# SMA-Q2_replacement_board_v2_3different.net
KiCad netlist of a schematic drawn in EAGLE
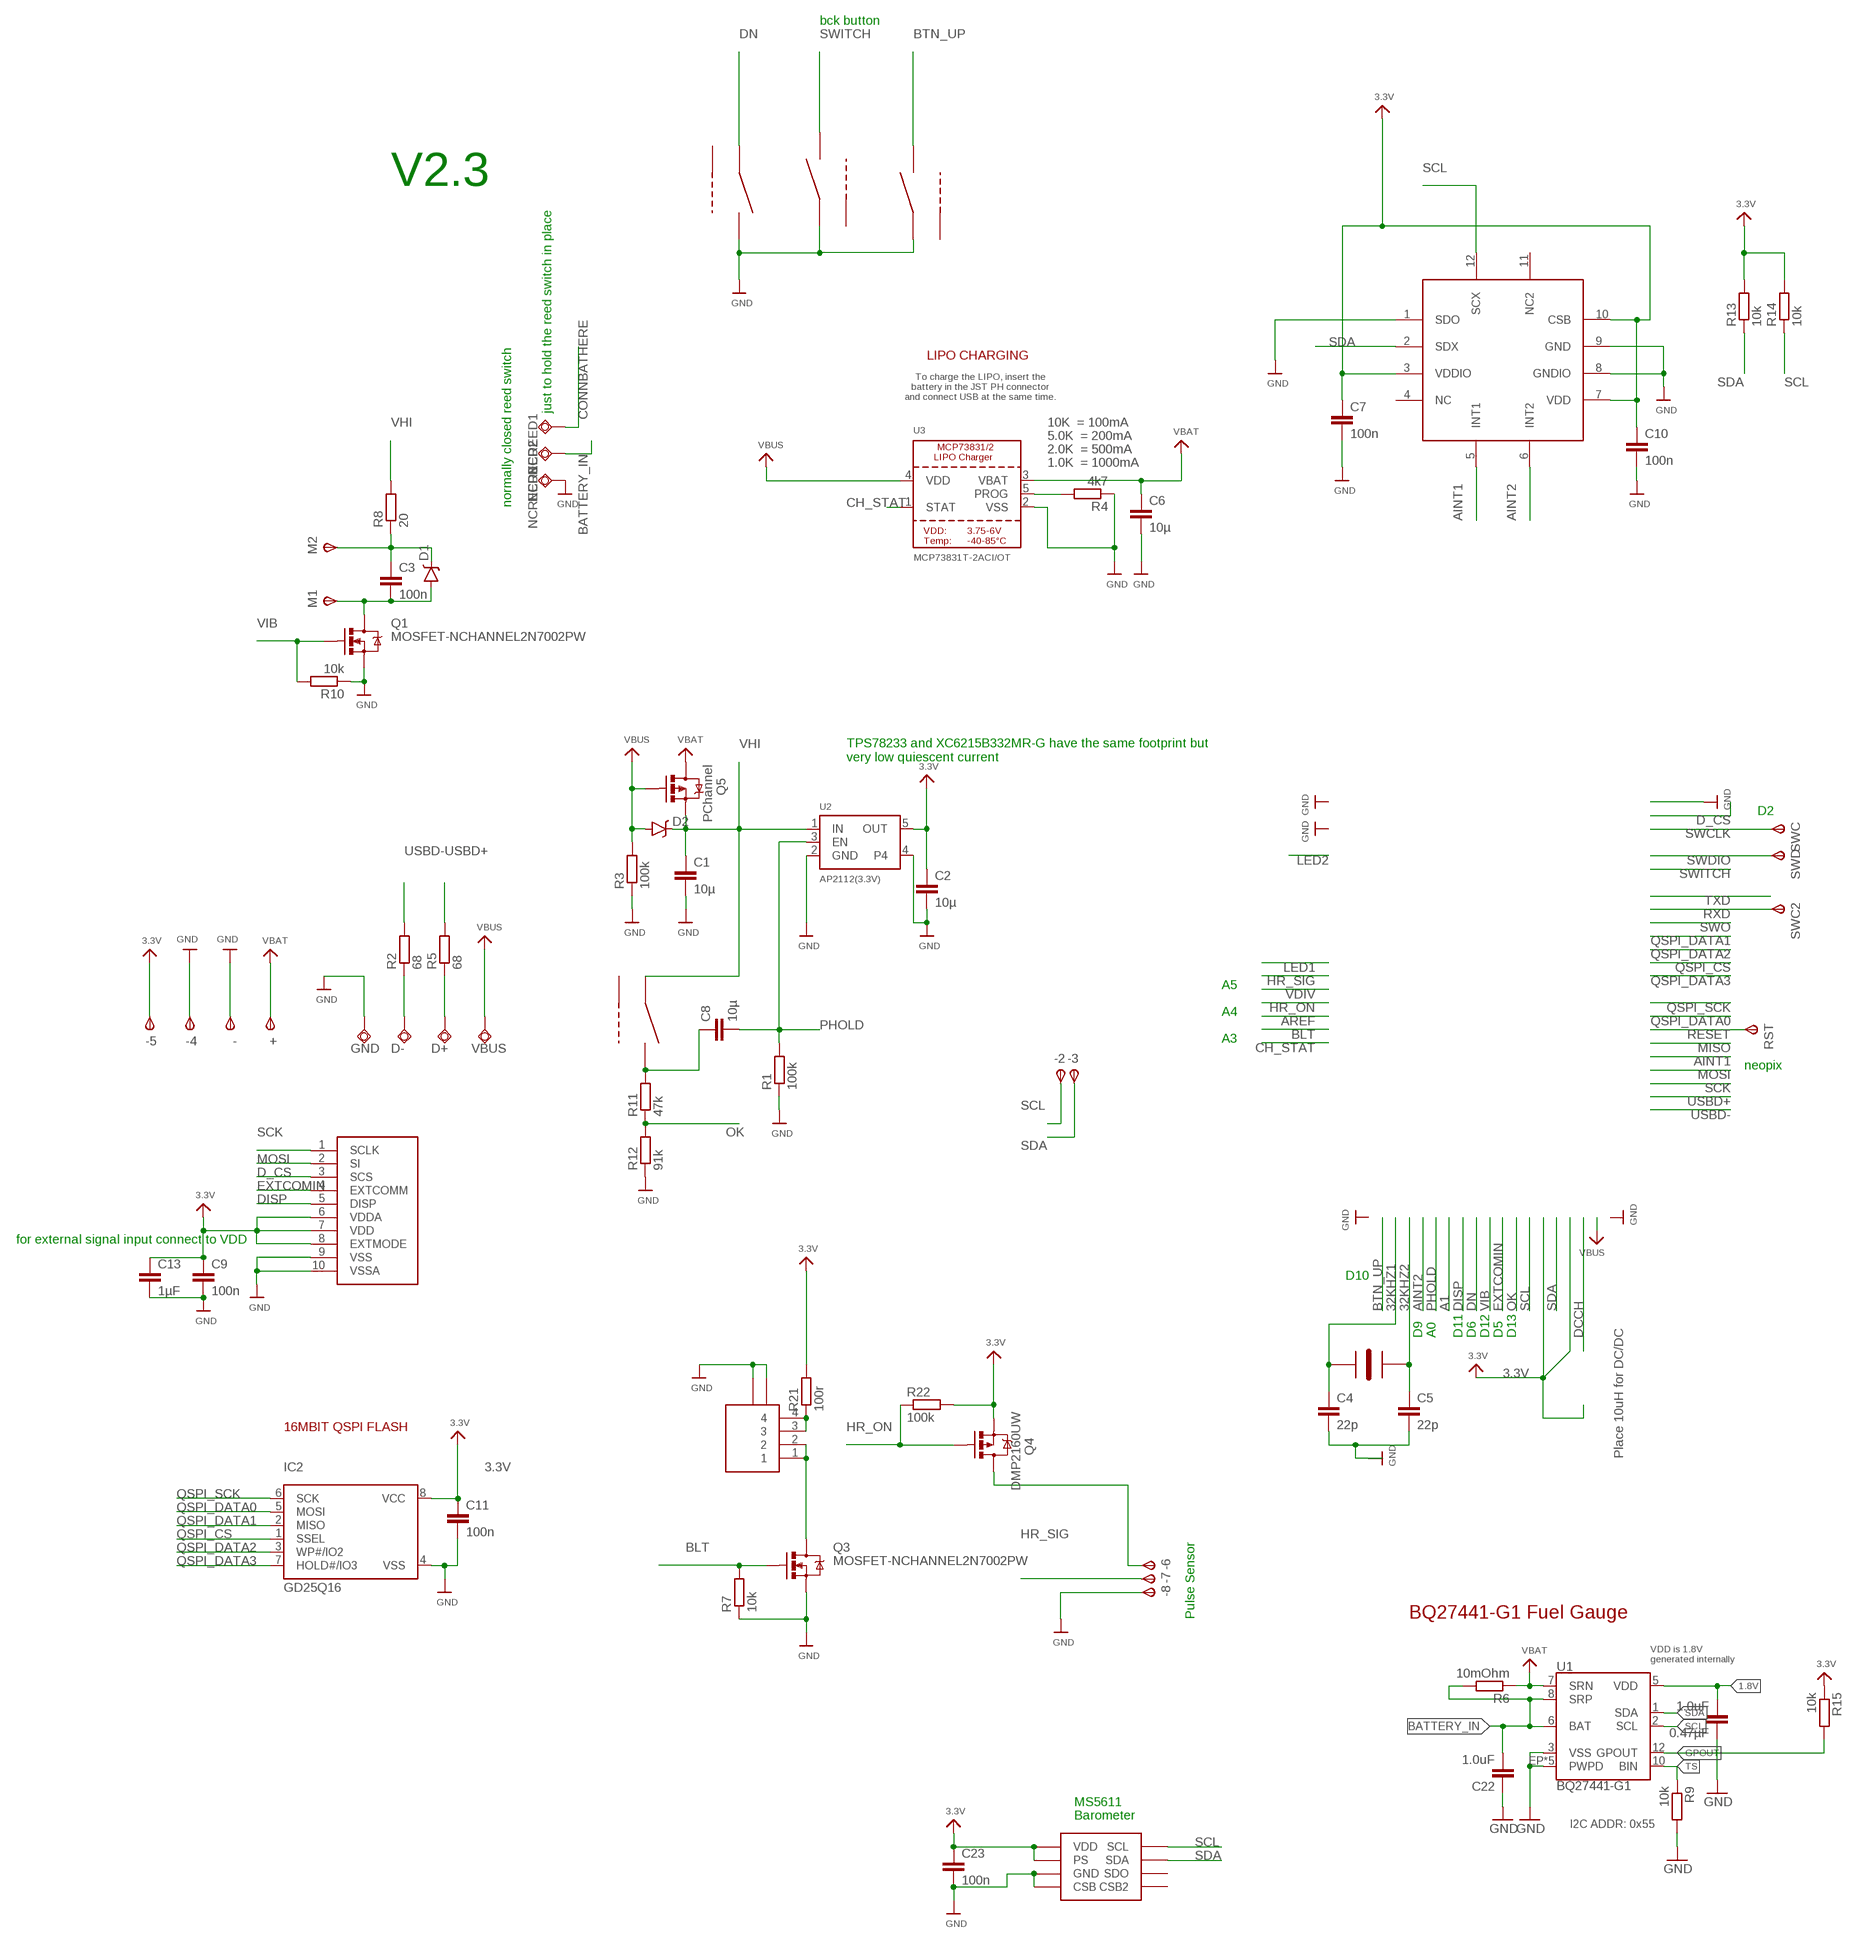
[diagram p0: schematic, sheet 1, part 1 of 2]
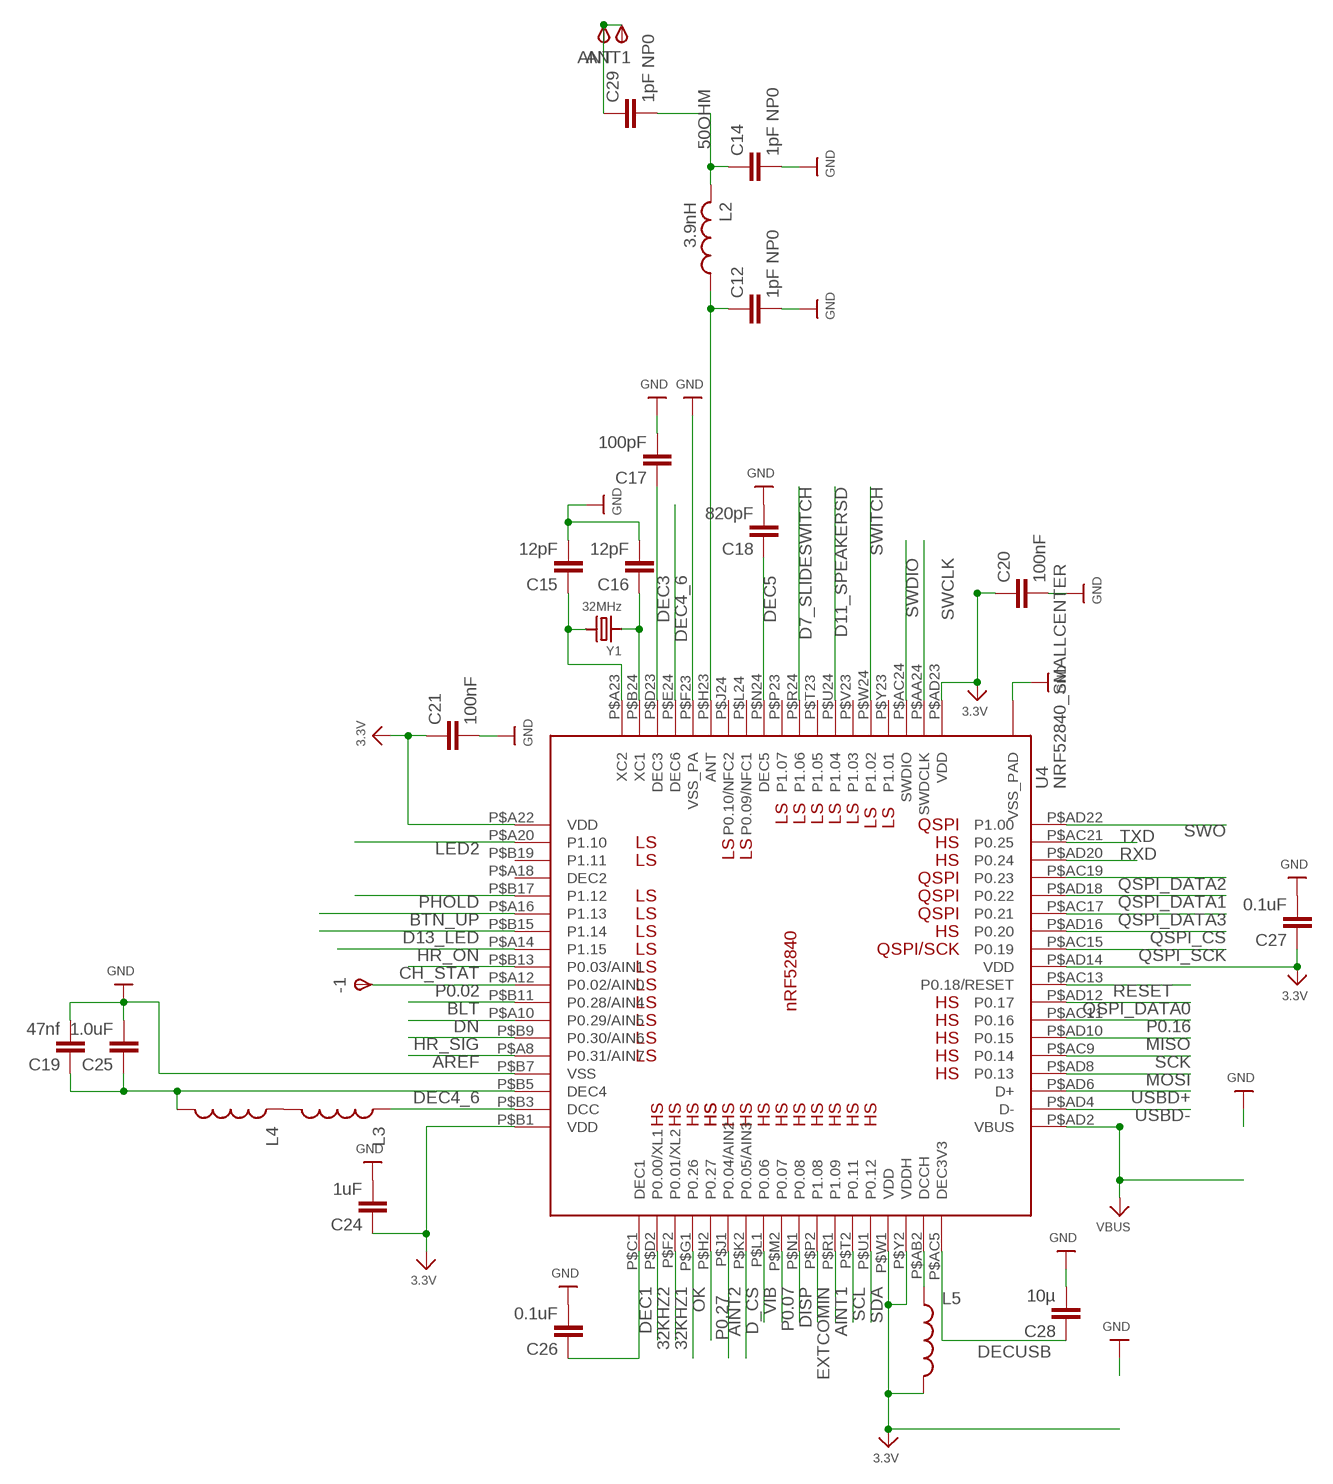
[diagram p1: schematic, sheet 1, part 2 of 2]

(export (version "E")
  (design (tool "Eeschema 10.0.6"))
  (components
    (comp (ref "+")
      (value "TPSTP09R")
      (footprint "eagle-import:TP09R")
      (libsource (lib "eagle-import") (part "TPSTP09R"))
    )
    (comp (ref "-")
      (value "TPSTP09R")
      (footprint "eagle-import:TP09R")
      (libsource (lib "eagle-import") (part "TPSTP09R"))
    )
    (comp (ref "-1")
      (value "TPSTP09R")
      (footprint "eagle-import:TP09R")
      (libsource (lib "eagle-import") (part "TPSTP09R"))
    )
    (comp (ref "-2")
      (value "TPSTP09R")
      (footprint "eagle-import:TP09R")
      (libsource (lib "eagle-import") (part "TPSTP09R"))
    )
    (comp (ref "-3")
      (value "TPSTP09R")
      (footprint "eagle-import:TP09R")
      (libsource (lib "eagle-import") (part "TPSTP09R"))
    )
    (comp (ref "-4")
      (value "TPSTP09R")
      (footprint "eagle-import:TP09R")
      (libsource (lib "eagle-import") (part "TPSTP09R"))
    )
    (comp (ref "-5")
      (value "TPSTP09R")
      (footprint "eagle-import:TP09R")
      (libsource (lib "eagle-import") (part "TPSTP09R"))
    )
    (comp (ref "-6")
      (value "TPSTP09R")
      (footprint "eagle-import:TP09R")
      (libsource (lib "eagle-import") (part "TPSTP09R"))
    )
    (comp (ref "-7")
      (value "TPSTP09R")
      (footprint "eagle-import:TP09R")
      (libsource (lib "eagle-import") (part "TPSTP09R"))
    )
    (comp (ref "-8")
      (value "TPSTP09R")
      (footprint "eagle-import:TP09R")
      (libsource (lib "eagle-import") (part "TPSTP09R"))
    )
    (comp (ref "0.47µF")
      (value "1.0uF")
      (footprint "eagle-import:RESC0603_N")
      (libsource (lib "eagle-import") (part "CAPACITOR_0603_N"))
    )
    (comp (ref "ANT")
      (value "TPSTP19SQ")
      (footprint "eagle-import:TP19SQ")
      (libsource (lib "eagle-import") (part "TPSTP19SQ"))
    )
    (comp (ref "ANT1")
      (value "TPSTP19SQ")
      (footprint "eagle-import:TP19SQ")
      (libsource (lib "eagle-import") (part "TPSTP19SQ"))
    )
    (comp (ref "C1")
      (value "10µ")
      (footprint "eagle-import:C0603")
      (libsource (lib "eagle-import") (part "C-EUC0603"))
    )
    (comp (ref "C2")
      (value "10µ")
      (footprint "eagle-import:C0603")
      (libsource (lib "eagle-import") (part "C-EUC0603"))
    )
    (comp (ref "C3")
      (value "100n")
      (footprint "eagle-import:C0402")
      (libsource (lib "eagle-import") (part "C-EUC0402"))
    )
    (comp (ref "C4")
      (value "22p")
      (footprint "eagle-import:C0402")
      (libsource (lib "eagle-import") (part "C-EUC0402"))
    )
    (comp (ref "C5")
      (value "22p")
      (footprint "eagle-import:C0402")
      (libsource (lib "eagle-import") (part "C-EUC0402"))
    )
    (comp (ref "C6")
      (value "10µ")
      (footprint "eagle-import:C0603")
      (libsource (lib "eagle-import") (part "C-EUC0603"))
    )
    (comp (ref "C7")
      (value "100n")
      (footprint "eagle-import:C0402")
      (libsource (lib "eagle-import") (part "C-EUC0402"))
    )
    (comp (ref "C8")
      (value "10µ")
      (footprint "eagle-import:C0603")
      (libsource (lib "eagle-import") (part "C-EUC0603"))
    )
    (comp (ref "C9")
      (value "100n")
      (footprint "eagle-import:C0402")
      (libsource (lib "eagle-import") (part "C-EUC0402"))
    )
    (comp (ref "C10")
      (value "100n")
      (footprint "eagle-import:C0402")
      (libsource (lib "eagle-import") (part "C-EUC0402"))
    )
    (comp (ref "C11")
      (value "100n")
      (footprint "eagle-import:C0402")
      (libsource (lib "eagle-import") (part "C-EUC0402"))
    )
    (comp (ref "C12")
      (value "1pF NP0")
      (footprint "eagle-import:RESC0402_N")
      (libsource (lib "eagle-import") (part "CAPACITOR_0402_N"))
    )
    (comp (ref "C13")
      (value "1µF")
      (footprint "eagle-import:C0402")
      (libsource (lib "eagle-import") (part "C-EUC0402"))
    )
    (comp (ref "C14")
      (value "1pF NP0")
      (footprint "eagle-import:RESC0402_N")
      (libsource (lib "eagle-import") (part "CAPACITOR_0402_N"))
    )
    (comp (ref "C15")
      (value "12pF")
      (footprint "eagle-import:RESC0402_N")
      (libsource (lib "eagle-import") (part "CAPACITOR_0402_N"))
    )
    (comp (ref "C16")
      (value "12pF")
      (footprint "eagle-import:RESC0402_N")
      (libsource (lib "eagle-import") (part "CAPACITOR_0402_N"))
    )
    (comp (ref "C17")
      (value "100pF")
      (footprint "eagle-import:RESC0402_N")
      (libsource (lib "eagle-import") (part "CAPACITOR_0402_N"))
    )
    (comp (ref "C18")
      (value "820pF")
      (footprint "eagle-import:RESC0402_N")
      (libsource (lib "eagle-import") (part "CAPACITOR_0402_N"))
    )
    (comp (ref "C19")
      (value "47nf")
      (footprint "eagle-import:RESC0603_N")
      (libsource (lib "eagle-import") (part "CAPACITOR_0603_N"))
    )
    (comp (ref "C20")
      (value "100nF")
      (footprint "eagle-import:RESC0402_N")
      (libsource (lib "eagle-import") (part "CAPACITOR_0402_N"))
    )
    (comp (ref "C21")
      (value "100nF")
      (footprint "eagle-import:RESC0402_N")
      (libsource (lib "eagle-import") (part "CAPACITOR_0402_N"))
    )
    (comp (ref "C22")
      (value "1.0uF")
      (footprint "eagle-import:RESC0603_N")
      (libsource (lib "eagle-import") (part "CAPACITOR_0603_N"))
    )
    (comp (ref "C23")
      (value "100n")
      (footprint "eagle-import:C0402")
      (libsource (lib "eagle-import") (part "C-EUC0402"))
    )
    (comp (ref "C24")
      (value "1uF")
      (footprint "eagle-import:RESC0603_N")
      (libsource (lib "eagle-import") (part "CAPACITOR_0603_N"))
    )
    (comp (ref "C25")
      (value "1.0uF")
      (footprint "eagle-import:RESC0603_N")
      (libsource (lib "eagle-import") (part "CAPACITOR_0603_N"))
    )
    (comp (ref "C26")
      (value "0.1uF")
      (footprint "eagle-import:RESC0603_N")
      (libsource (lib "eagle-import") (part "CAPACITOR_0603_N"))
    )
    (comp (ref "C27")
      (value "0.1uF")
      (footprint "eagle-import:RESC0402_N")
      (libsource (lib "eagle-import") (part "CAPACITOR_0402_N"))
    )
    (comp (ref "C28")
      (value "10µ")
      (footprint "eagle-import:C0603")
      (libsource (lib "eagle-import") (part "C-EUC0603"))
    )
    (comp (ref "C29")
      (value "1pF NP0")
      (footprint "eagle-import:RESC0402_N")
      (libsource (lib "eagle-import") (part "CAPACITOR_0402_N"))
    )
    (comp (ref "D+")
      (value "TPSQTP20R")
      (footprint "eagle-import:TP20R")
      (libsource (lib "eagle-import") (part "TPSQTP20R"))
    )
    (comp (ref "D-")
      (value "TPSQTP20R")
      (footprint "eagle-import:TP20R")
      (libsource (lib "eagle-import") (part "TPSQTP20R"))
    )
    (comp (ref "D1")
      (value "BAT20J")
      (footprint "eagle-import:SOD-323")
      (libsource (lib "eagle-import") (part "DIODE-SCHOTTKY-BAT20J"))
    )
    (comp (ref "D2")
      (value "BAT20J")
      (footprint "eagle-import:SOD-323")
      (libsource (lib "eagle-import") (part "DIODE-SCHOTTKY-BAT20J"))
    )
    (comp (ref "DWN")
      (value "LS12T2")
      (footprint "eagle-import:LS12T2")
      (libsource (lib "eagle-import") (part "LS12T2"))
    )
    (comp (ref "DWN1")
      (value "LS12T2")
      (footprint "eagle-import:LS12T2")
      (libsource (lib "eagle-import") (part "LS12T2"))
    )
    (comp (ref "DWN2")
      (value "LS12T2")
      (footprint "eagle-import:LS12T2")
      (libsource (lib "eagle-import") (part "LS12T2"))
    )
    (comp (ref "DWN3")
      (value "LS12T2")
      (footprint "eagle-import:LS12T2")
      (libsource (lib "eagle-import") (part "LS12T2"))
    )
    (comp (ref "GND")
      (value "TPSQTP20R")
      (footprint "eagle-import:TP20R")
      (libsource (lib "eagle-import") (part "TPSQTP20R"))
    )
    (comp (ref "IC2")
      (value "GD25Q16")
      (footprint "eagle-import:USON8")
      (libsource (lib "eagle-import") (part "SPIFLASH_8PINUX"))
    )
    (comp (ref "L2")
      (value "3.9nH")
      (footprint "eagle-import:RESC0402_N")
      (libsource (lib "eagle-import") (part "INDUCTOR_0402_N"))
    )
    (comp (ref "L3")
      (value "INDUCTOR30OHM,1.8A")
      (footprint "eagle-import:0603")
      (libsource (lib "eagle-import") (part "INDUCTOR30OHM,1.8A"))
    )
    (comp (ref "L4")
      (value "INDUCTOR0402")
      (footprint "eagle-import:C0402")
      (libsource (lib "eagle-import") (part "INDUCTOR0402"))
    )
    (comp (ref "L5")
      (value "INDUCTOR30OHM,1.8A")
      (footprint "eagle-import:0603")
      (libsource (lib "eagle-import") (part "INDUCTOR30OHM,1.8A"))
    )
    (comp (ref "M1")
      (value "TPSTP09R")
      (footprint "eagle-import:TP09R")
      (libsource (lib "eagle-import") (part "TPSTP09R"))
    )
    (comp (ref "M2")
      (value "TPSTP09R")
      (footprint "eagle-import:TP09R")
      (libsource (lib "eagle-import") (part "TPSTP09R"))
    )
    (comp (ref "NCREED1")
      (value "TPSQTP20R")
      (footprint "eagle-import:TP20R")
      (libsource (lib "eagle-import") (part "TPSQTP20R"))
    )
    (comp (ref "NCREED2")
      (value "TPSQTP20R")
      (footprint "eagle-import:TP20R")
      (libsource (lib "eagle-import") (part "TPSQTP20R"))
    )
    (comp (ref "NCREED3")
      (value "TPSQTP20R")
      (footprint "eagle-import:TP20R")
      (libsource (lib "eagle-import") (part "TPSQTP20R"))
    )
    (comp (ref "Q1")
      (value "MOSFET-NCHANNEL2N7002PW")
      (footprint "eagle-import:SOT323")
      (libsource (lib "eagle-import") (part "MOSFET-NCHANNEL2N7002PW"))
    )
    (comp (ref "Q3")
      (value "MOSFET-NCHANNEL2N7002PW")
      (footprint "eagle-import:SOT323")
      (libsource (lib "eagle-import") (part "MOSFET-NCHANNEL2N7002PW"))
    )
    (comp (ref "Q4")
      (value "DMP2160UW")
      (footprint "eagle-import:SOT323")
      (libsource (lib "eagle-import") (part "MOSFET-P-CHANNEL-DMP2160UW"))
    )
    (comp (ref "Q5")
      (value "PChannel")
      (footprint "eagle-import:SOT323")
      (libsource (lib "eagle-import") (part "MOSFET-P-CHANNEL-DMP2160UW"))
    )
    (comp (ref "R1")
      (value "100k")
      (footprint "eagle-import:R0402")
      (libsource (lib "eagle-import") (part "R-EU_R0402"))
    )
    (comp (ref "R2")
      (value "68")
      (footprint "eagle-import:R0402")
      (libsource (lib "eagle-import") (part "R-EU_R0402"))
    )
    (comp (ref "R3")
      (value "100k")
      (footprint "eagle-import:R0402")
      (libsource (lib "eagle-import") (part "R-EU_R0402"))
    )
    (comp (ref "R4")
      (value "4k7")
      (footprint "eagle-import:R0402")
      (libsource (lib "eagle-import") (part "R-EU_R0402"))
    )
    (comp (ref "R5")
      (value "68")
      (footprint "eagle-import:R0402")
      (libsource (lib "eagle-import") (part "R-EU_R0402"))
    )
    (comp (ref "R6")
      (value "10mOhm")
      (footprint "eagle-import:R0402")
      (libsource (lib "eagle-import") (part "R-EU_R0402"))
    )
    (comp (ref "R7")
      (value "10k")
      (footprint "eagle-import:R0402")
      (libsource (lib "eagle-import") (part "R-EU_R0402"))
    )
    (comp (ref "R8")
      (value "20")
      (footprint "eagle-import:R0402")
      (libsource (lib "eagle-import") (part "R-EU_R0402"))
    )
    (comp (ref "R9")
      (value "10k")
      (footprint "eagle-import:R0402")
      (libsource (lib "eagle-import") (part "R-EU_R0402"))
    )
    (comp (ref "R10")
      (value "10k")
      (footprint "eagle-import:R0402")
      (libsource (lib "eagle-import") (part "R-EU_R0402"))
    )
    (comp (ref "R11")
      (value "47k")
      (footprint "eagle-import:R0402")
      (libsource (lib "eagle-import") (part "R-EU_R0402"))
    )
    (comp (ref "R12")
      (value "91k")
      (footprint "eagle-import:R0402")
      (libsource (lib "eagle-import") (part "R-EU_R0402"))
    )
    (comp (ref "R13")
      (value "10k")
      (footprint "eagle-import:R0402")
      (libsource (lib "eagle-import") (part "R-EU_R0402"))
    )
    (comp (ref "R14")
      (value "10k")
      (footprint "eagle-import:R0402")
      (libsource (lib "eagle-import") (part "R-EU_R0402"))
    )
    (comp (ref "R15")
      (value "10k")
      (footprint "eagle-import:R0402")
      (libsource (lib "eagle-import") (part "R-EU_R0402"))
    )
    (comp (ref "R21")
      (value "100r")
      (footprint "eagle-import:R0402")
      (libsource (lib "eagle-import") (part "R-EU_R0402"))
    )
    (comp (ref "R22")
      (value "100k")
      (footprint "eagle-import:R0402")
      (libsource (lib "eagle-import") (part "R-EU_R0402"))
    )
    (comp (ref "RST")
      (value "TPSTP09R")
      (footprint "eagle-import:TP09R")
      (libsource (lib "eagle-import") (part "TPSTP09R"))
    )
    (comp (ref "SWC")
      (value "TPSTP09R")
      (footprint "eagle-import:TP09R")
      (libsource (lib "eagle-import") (part "TPSTP09R"))
    )
    (comp (ref "SWC2")
      (value "TPSTP09R")
      (footprint "eagle-import:TP09R")
      (libsource (lib "eagle-import") (part "TPSTP09R"))
    )
    (comp (ref "SWD")
      (value "TPSTP09R")
      (footprint "eagle-import:TP09R")
      (libsource (lib "eagle-import") (part "TPSTP09R"))
    )
    (comp (ref "U$2")
      (value "SHARP_MEM_DISP")
      (footprint "eagle-import:Y5BW")
      (libsource (lib "eagle-import") (part "SHARP_MEM_DISP"))
    )
    (comp (ref "U$6")
      (value "Y5B-4PIN")
      (footprint "eagle-import:Y5B-4PIN")
      (libsource (lib "eagle-import") (part "Y5B-4PIN"))
    )
    (comp (ref "U$7")
      (value "BMA400")
      (footprint "eagle-import:BMA400")
      (libsource (lib "eagle-import") (part "BMA400"))
    )
    (comp (ref "U$45")
      (value "MC5611")
      (footprint "eagle-import:MS5611")
      (libsource (lib "eagle-import") (part "MC5611"))
    )
    (comp (ref "U$81")
      (value "ECX-1210")
      (footprint "eagle-import:ECX-1210")
      (libsource (lib "eagle-import") (part "ECX-1210"))
    )
    (comp (ref "U1")
      (value "BQ27441-G1")
      (footprint "eagle-import:PDSO-N12")
      (libsource (lib "eagle-import") (part "BQ27441-G1"))
    )
    (comp (ref "U2")
      (value "AP2112(3.3V)")
      (footprint "eagle-import:SOT23-5")
      (libsource (lib "eagle-import") (part "VREG_SOT23-5"))
    )
    (comp (ref "U3")
      (value "MCP73831T-2ACI/OT")
      (footprint "eagle-import:SOT23-5")
      (libsource (lib "eagle-import") (part "MCP73831/2"))
    )
    (comp (ref "U4")
      (value "NRF52840_SMALLCENTER")
      (footprint "eagle-import:AQFN50P700X800X85_HS-74N_SMALLCENTER")
      (libsource (lib "eagle-import") (part "NRF52840_SMALLCENTER"))
    )
    (comp (ref "VBUS")
      (value "TPSQTP20R")
      (footprint "eagle-import:TP20R")
      (libsource (lib "eagle-import") (part "TPSQTP20R"))
    )
    (comp (ref "Y1")
      (value "32MHz")
      (footprint "eagle-import:CRYSTAL_2.5X2")
      (libsource (lib "eagle-import") (part "CRYSTAL2.5X2.0"))
    )
  )
  (nets
    (net (code "1") (name "/32KHZ1") (class "Default")
      (node (ref "C4") (pin "1") (pinfunction "1_1") (pintype "passive"))
      (node (ref "U$81") (pin "P$1") (pinfunction "P$1_P$1") (pintype "bidirectional"))
      (node (ref "U4") (pin "P$F2") (pinfunction "P0.01/XL2_P$F2") (pintype "bidirectional"))
    )
    (net (code "2") (name "/32KHZ2") (class "Default")
      (node (ref "C5") (pin "1") (pinfunction "1_1") (pintype "passive"))
      (node (ref "U$81") (pin "P$2") (pinfunction "P$2_P$2") (pintype "bidirectional"))
      (node (ref "U4") (pin "P$D2") (pinfunction "P0.00/XL1_P$D2") (pintype "bidirectional"))
    )
    (net (code "3") (name "/50OHM") (class "Default")
      (node (ref "C14") (pin "1") (pinfunction "1_1") (pintype "passive"))
      (node (ref "C29") (pin "2") (pinfunction "2_2") (pintype "passive"))
      (node (ref "L2") (pin "2") (pinfunction "2_2") (pintype "passive"))
    )
    (net (code "5") (name "/AINT1") (class "Default")
      (node (ref "U$7") (pin "5") (pinfunction "INT1_5") (pintype "bidirectional"))
      (node (ref "U4") (pin "P$R1") (pinfunction "P1.09_P$R1") (pintype "bidirectional"))
    )
    (net (code "6") (name "/AINT2") (class "Default")
      (node (ref "U$7") (pin "6") (pinfunction "INT2_6") (pintype "bidirectional"))
      (node (ref "U4") (pin "P$J1") (pinfunction "P0.04/AIN2_P$J1") (pintype "bidirectional"))
    )
    (net (code "7") (name "/AREF") (class "Default")
      (node (ref "U4") (pin "P$A8") (pinfunction "P0.31/AIN7_P$A8") (pintype "bidirectional"))
    )
    (net (code "8") (name "/BLT") (class "Default")
      (node (ref "Q3") (pin "1") (pinfunction "G_1") (pintype "passive"))
      (node (ref "R7") (pin "2") (pinfunction "2_2") (pintype "passive"))
      (node (ref "U4") (pin "P$B11") (pinfunction "P0.28/AIN4_P$B11") (pintype "bidirectional"))
    )
    (net (code "9") (name "/BTN_UP") (class "Default")
      (node (ref "DWN2") (pin "1") (pinfunction "1_1") (pintype "bidirectional"))
      (node (ref "U4") (pin "P$A16") (pinfunction "P1.13_P$A16") (pintype "bidirectional"))
    )
    (net (code "10") (name "/CH_STAT") (class "Default")
      (node (ref "U3") (pin "1") (pinfunction "STAT_1") (pintype "output"))
      (node (ref "U4") (pin "P$B13") (pinfunction "P0.03/AIN1_P$B13") (pintype "bidirectional"))
    )
    (net (code "11") (name "/CONNBATHERE") (class "Default")
      (node (ref "NCREED1") (pin "TP") (pinfunction "TP_TP") (pintype "input"))
    )
    (net (code "12") (name "/D7_SLIDESWITCH") (class "Default")
      (node (ref "U4") (pin "P$R24") (pinfunction "P1.06_P$R24") (pintype "bidirectional"))
    )
    (net (code "13") (name "/D11_SPEAKERSD") (class "Default")
      (node (ref "U4") (pin "P$U24") (pinfunction "P1.04_P$U24") (pintype "bidirectional"))
    )
    (net (code "14") (name "/D13_LED") (class "Default")
      (node (ref "U4") (pin "P$B15") (pinfunction "P1.14_P$B15") (pintype "bidirectional"))
    )
    (net (code "16") (name "/DEC1") (class "Default")
      (node (ref "C26") (pin "1") (pinfunction "1_1") (pintype "passive"))
      (node (ref "U4") (pin "P$C1") (pinfunction "DEC1_P$C1") (pintype "power_in"))
    )
    (net (code "17") (name "/DEC3") (class "Default")
      (node (ref "C17") (pin "1") (pinfunction "1_1") (pintype "passive"))
      (node (ref "U4") (pin "P$D23") (pinfunction "DEC3_P$D23") (pintype "bidirectional"))
    )
    (net (code "18") (name "/DEC4_6") (class "Default")
      (node (ref "C19") (pin "1") (pinfunction "1_1") (pintype "passive"))
      (node (ref "C25") (pin "1") (pinfunction "1_1") (pintype "passive"))
      (node (ref "L4") (pin "2") (pinfunction "2_2") (pintype "passive"))
      (node (ref "U4") (pin "P$B5") (pinfunction "DEC4_P$B5") (pintype "power_in"))
      (node (ref "U4") (pin "P$E24") (pinfunction "DEC6_P$E24") (pintype "bidirectional"))
    )
    (net (code "19") (name "/DEC5") (class "Default")
      (node (ref "C18") (pin "1") (pinfunction "1_1") (pintype "passive"))
      (node (ref "U4") (pin "P$N24") (pinfunction "DEC5_P$N24") (pintype "bidirectional"))
    )
    (net (code "20") (name "/DECUSB") (class "Default")
      (node (ref "C28") (pin "1") (pinfunction "1_1") (pintype "passive"))
      (node (ref "U4") (pin "P$AC5") (pinfunction "DEC3V3_P$AC5") (pintype "bidirectional"))
    )
    (net (code "21") (name "/DISP") (class "Default")
      (node (ref "U$2") (pin "5") (pinfunction "DISP_5") (pintype "bidirectional"))
      (node (ref "U4") (pin "P$N1") (pinfunction "P0.08_P$N1") (pintype "bidirectional"))
    )
    (net (code "22") (name "/DN") (class "Default")
      (node (ref "DWN") (pin "2") (pinfunction "2_2") (pintype "bidirectional"))
      (node (ref "U4") (pin "P$A10") (pinfunction "P0.29/AIN5_P$A10") (pintype "bidirectional"))
    )
    (net (code "23") (name "/D_CS") (class "Default")
      (node (ref "U$2") (pin "3") (pinfunction "SCS_3") (pintype "bidirectional"))
      (node (ref "U4") (pin "P$K2") (pinfunction "P0.05/AIN3_P$K2") (pintype "bidirectional"))
    )
    (net (code "24") (name "/EXTCOMIN") (class "Default")
      (node (ref "U$2") (pin "4") (pinfunction "EXTCOMM_4") (pintype "bidirectional"))
      (node (ref "U4") (pin "P$P2") (pinfunction "P1.08_P$P2") (pintype "bidirectional"))
    )
    (net (code "25") (name "/HR_ON") (class "Default")
      (node (ref "Q4") (pin "1") (pinfunction "G_1") (pintype "passive"))
      (node (ref "R22") (pin "1") (pinfunction "1_1") (pintype "passive"))
      (node (ref "U4") (pin "P$A14") (pinfunction "P1.15_P$A14") (pintype "bidirectional"))
    )
    (net (code "26") (name "/HR_SIG") (class "Default")
      (node (ref "-7") (pin "TP") (pinfunction "PP_TP") (pintype "input"))
      (node (ref "U4") (pin "P$B9") (pinfunction "P0.30/AIN6_P$B9") (pintype "bidirectional"))
    )
    (net (code "28") (name "/LED2") (class "Default")
      (node (ref "U4") (pin "P$A20") (pinfunction "P1.10_P$A20") (pintype "bidirectional"))
    )
    (net (code "29") (name "/MISO") (class "Default")
      (node (ref "U4") (pin "P$AD10") (pinfunction "P0.15_P$AD10") (pintype "bidirectional"))
    )
    (net (code "30") (name "/MOSI") (class "Default")
      (node (ref "U$2") (pin "2") (pinfunction "SI_2") (pintype "bidirectional"))
      (node (ref "U4") (pin "P$AD8") (pinfunction "P0.13_P$AD8") (pintype "bidirectional"))
    )
    (net (code "31") (name "/OK") (class "Default")
      (node (ref "R11") (pin "1") (pinfunction "1_1") (pintype "passive"))
      (node (ref "R12") (pin "2") (pinfunction "2_2") (pintype "passive"))
      (node (ref "U4") (pin "P$G1") (pinfunction "P0.26_P$G1") (pintype "bidirectional"))
    )
    (net (code "32") (name "/P0.02") (class "Default")
      (node (ref "-1") (pin "TP") (pinfunction "PP_TP") (pintype "input"))
      (node (ref "U4") (pin "P$A12") (pinfunction "P0.02/AIN0_P$A12") (pintype "bidirectional"))
    )
    (net (code "33") (name "/P0.07") (class "Default")
      (node (ref "U4") (pin "P$M2") (pinfunction "P0.07_P$M2") (pintype "bidirectional"))
    )
    (net (code "34") (name "/P0.16") (class "Default")
      (node (ref "U4") (pin "P$AC11") (pinfunction "P0.16_P$AC11") (pintype "bidirectional"))
    )
    (net (code "35") (name "/P0.27") (class "Default")
      (node (ref "U4") (pin "P$H2") (pinfunction "P0.27_P$H2") (pintype "bidirectional"))
    )
    (net (code "36") (name "/PHOLD") (class "Default")
      (node (ref "C8") (pin "2") (pinfunction "2_2") (pintype "passive"))
      (node (ref "R1") (pin "2") (pinfunction "2_2") (pintype "passive"))
      (node (ref "U2") (pin "3") (pinfunction "EN_3") (pintype "input"))
      (node (ref "U4") (pin "P$B17") (pinfunction "P1.12_P$B17") (pintype "bidirectional"))
    )
    (net (code "37") (name "/QSPI_CS") (class "Default")
      (node (ref "IC2") (pin "1") (pinfunction "SSEL_1") (pintype "bidirectional"))
      (node (ref "U4") (pin "P$AD16") (pinfunction "P0.20_P$AD16") (pintype "bidirectional"))
    )
    (net (code "38") (name "/QSPI_DATA0") (class "Default")
      (node (ref "IC2") (pin "5") (pinfunction "MOSI_5") (pintype "bidirectional"))
      (node (ref "U4") (pin "P$AD12") (pinfunction "P0.17_P$AD12") (pintype "bidirectional"))
    )
    (net (code "39") (name "/QSPI_DATA1") (class "Default")
      (node (ref "IC2") (pin "2") (pinfunction "MISO_2") (pintype "bidirectional"))
      (node (ref "U4") (pin "P$AD18") (pinfunction "P0.22_P$AD18") (pintype "bidirectional"))
    )
    (net (code "40") (name "/QSPI_DATA2") (class "Default")
      (node (ref "IC2") (pin "3") (pinfunction "WP#/IO2_3") (pintype "bidirectional"))
      (node (ref "U4") (pin "P$AC19") (pinfunction "P0.23_P$AC19") (pintype "bidirectional"))
    )
    (net (code "41") (name "/QSPI_DATA3") (class "Default")
      (node (ref "IC2") (pin "7") (pinfunction "HOLD#/IO3_7") (pintype "bidirectional"))
      (node (ref "U4") (pin "P$AC17") (pinfunction "P0.21_P$AC17") (pintype "bidirectional"))
    )
    (net (code "42") (name "/QSPI_SCK") (class "Default")
      (node (ref "IC2") (pin "6") (pinfunction "SCK_6") (pintype "bidirectional"))
      (node (ref "U4") (pin "P$AC15") (pinfunction "P0.19_P$AC15") (pintype "bidirectional"))
    )
    (net (code "43") (name "/RESET") (class "Default")
      (node (ref "RST") (pin "TP") (pinfunction "PP_TP") (pintype "input"))
      (node (ref "U4") (pin "P$AC13") (pinfunction "P0.18/RESET_P$AC13") (pintype "bidirectional"))
    )
    (net (code "44") (name "/RXD") (class "Default")
      (node (ref "SWC2") (pin "TP") (pinfunction "PP_TP") (pintype "input"))
      (node (ref "U4") (pin "P$AD20") (pinfunction "P0.24_P$AD20") (pintype "bidirectional"))
    )
    (net (code "45") (name "/SCK") (class "Default")
      (node (ref "U$2") (pin "1") (pinfunction "SCLK_1") (pintype "bidirectional"))
      (node (ref "U4") (pin "P$AC9") (pinfunction "P0.14_P$AC9") (pintype "bidirectional"))
    )
    (net (code "46") (name "/SWCLK") (class "Default")
      (node (ref "SWC") (pin "TP") (pinfunction "PP_TP") (pintype "input"))
      (node (ref "U4") (pin "P$AA24") (pinfunction "SWDCLK_P$AA24") (pintype "input"))
    )
    (net (code "47") (name "/SWDIO") (class "Default")
      (node (ref "SWD") (pin "TP") (pinfunction "PP_TP") (pintype "input"))
      (node (ref "U4") (pin "P$AC24") (pinfunction "SWDIO_P$AC24") (pintype "bidirectional"))
    )
    (net (code "48") (name "/SWITCH") (class "Default")
      (node (ref "DWN1") (pin "1") (pinfunction "1_1") (pintype "bidirectional"))
      (node (ref "U4") (pin "P$W24") (pinfunction "P1.02_P$W24") (pintype "bidirectional"))
    )
    (net (code "49") (name "/SWO") (class "Default")
      (node (ref "U4") (pin "P$AD22") (pinfunction "P1.00_P$AD22") (pintype "bidirectional"))
    )
    (net (code "50") (name "/TXD") (class "Default")
      (node (ref "U4") (pin "P$AC21") (pinfunction "P0.25_P$AC21") (pintype "bidirectional"))
    )
    (net (code "51") (name "/USBD+") (class "Default")
      (node (ref "R5") (pin "2") (pinfunction "2_2") (pintype "passive"))
      (node (ref "U4") (pin "P$AD6") (pinfunction "D+_P$AD6") (pintype "bidirectional"))
    )
    (net (code "52") (name "/USBD-") (class "Default")
      (node (ref "R2") (pin "2") (pinfunction "2_2") (pintype "passive"))
      (node (ref "U4") (pin "P$AD4") (pinfunction "D-_P$AD4") (pintype "bidirectional"))
    )
    (net (code "54") (name "/VHI") (class "Default")
      (node (ref "C1") (pin "1") (pinfunction "1_1") (pintype "passive"))
      (node (ref "D2") (pin "C") (pinfunction "C_C") (pintype "passive"))
      (node (ref "DWN3") (pin "2") (pinfunction "2_2") (pintype "bidirectional"))
      (node (ref "Q5") (pin "2") (pinfunction "S_2") (pintype "passive"))
      (node (ref "R8") (pin "2") (pinfunction "2_2") (pintype "passive"))
      (node (ref "U2") (pin "1") (pinfunction "IN_1") (pintype "power_in"))
    )
    (net (code "55") (name "/VIB") (class "Default")
      (node (ref "Q1") (pin "1") (pinfunction "G_1") (pintype "passive"))
      (node (ref "R10") (pin "2") (pinfunction "2_2") (pintype "passive"))
      (node (ref "U4") (pin "P$L1") (pinfunction "P0.06_P$L1") (pintype "bidirectional"))
    )
    (net (code "56") (name "1.8V") (class "Default")
      (node (ref "0.47µF") (pin "2") (pinfunction "2_2") (pintype "passive"))
      (node (ref "U1") (pin "5") (pinfunction "VDD_5") (pintype "bidirectional"))
    )
    (net (code "57") (name "3.3V") (class "Default")
      (node (ref "-5") (pin "TP") (pinfunction "PP_TP") (pintype "input"))
      (node (ref "C10") (pin "1") (pinfunction "1_1") (pintype "passive"))
      (node (ref "C11") (pin "1") (pinfunction "1_1") (pintype "passive"))
      (node (ref "C13") (pin "1") (pinfunction "1_1") (pintype "passive"))
      (node (ref "C2") (pin "1") (pinfunction "1_1") (pintype "passive"))
      (node (ref "C20") (pin "1") (pinfunction "1_1") (pintype "passive"))
      (node (ref "C21") (pin "1") (pinfunction "1_1") (pintype "passive"))
      (node (ref "C23") (pin "1") (pinfunction "1_1") (pintype "passive"))
      (node (ref "C24") (pin "1") (pinfunction "1_1") (pintype "passive"))
      (node (ref "C27") (pin "1") (pinfunction "1_1") (pintype "passive"))
      (node (ref "C7") (pin "1") (pinfunction "1_1") (pintype "passive"))
      (node (ref "C9") (pin "1") (pinfunction "1_1") (pintype "passive"))
      (node (ref "IC2") (pin "8") (pinfunction "VCC_8") (pintype "bidirectional"))
      (node (ref "L5") (pin "2") (pinfunction "2_2") (pintype "passive"))
      (node (ref "Q4") (pin "2") (pinfunction "S_2") (pintype "passive"))
      (node (ref "R13") (pin "2") (pinfunction "2_2") (pintype "passive"))
      (node (ref "R14") (pin "2") (pinfunction "2_2") (pintype "passive"))
      (node (ref "R15") (pin "1") (pinfunction "1_1") (pintype "passive"))
      (node (ref "R21") (pin "2") (pinfunction "2_2") (pintype "passive"))
      (node (ref "R22") (pin "2") (pinfunction "2_2") (pintype "passive"))
      (node (ref "U$2") (pin "6") (pinfunction "VDDA_6") (pintype "bidirectional"))
      (node (ref "U$2") (pin "7") (pinfunction "VDD_7") (pintype "bidirectional"))
      (node (ref "U$2") (pin "8") (pinfunction "EXTMODE_8") (pintype "bidirectional"))
      (node (ref "U$45") (pin "PS") (pinfunction "PS_PS") (pintype "bidirectional"))
      (node (ref "U$45") (pin "VDD") (pinfunction "VDD_VDD") (pintype "bidirectional"))
      (node (ref "U$7") (pin "10") (pinfunction "CSB_10") (pintype "bidirectional"))
      (node (ref "U$7") (pin "3") (pinfunction "VDDIO_3") (pintype "bidirectional"))
      (node (ref "U$7") (pin "7") (pinfunction "VDD_7") (pintype "bidirectional"))
      (node (ref "U2") (pin "5") (pinfunction "OUT_5") (pintype "power_in"))
      (node (ref "U4") (pin "P$A22") (pinfunction "VDD_P$A22") (pintype "power_in"))
      (node (ref "U4") (pin "P$AD14") (pinfunction "VDD_P$AD14") (pintype "power_in"))
      (node (ref "U4") (pin "P$AD23") (pinfunction "VDD_P$AD23") (pintype "power_in"))
      (node (ref "U4") (pin "P$B1") (pinfunction "VDD_P$B1") (pintype "power_in"))
      (node (ref "U4") (pin "P$W1") (pinfunction "VDD_P$W1") (pintype "power_in"))
      (node (ref "U4") (pin "P$Y2") (pinfunction "VDDH_P$Y2") (pintype "power_in"))
    )
    (net (code "58") (name "BATTERY_IN") (class "Default")
      (node (ref "C22") (pin "2") (pinfunction "2_2") (pintype "passive"))
      (node (ref "NCREED2") (pin "TP") (pinfunction "TP_TP") (pintype "input"))
      (node (ref "R6") (pin "2") (pinfunction "2_2") (pintype "passive"))
      (node (ref "U1") (pin "6") (pinfunction "BAT_6") (pintype "bidirectional"))
      (node (ref "U1") (pin "8") (pinfunction "SRP_8") (pintype "bidirectional"))
    )
    (net (code "59") (name "GND") (class "Default")
      (node (ref "-") (pin "TP") (pinfunction "PP_TP") (pintype "input"))
      (node (ref "-4") (pin "TP") (pinfunction "PP_TP") (pintype "input"))
      (node (ref "-8") (pin "TP") (pinfunction "PP_TP") (pintype "input"))
      (node (ref "0.47µF") (pin "1") (pinfunction "1_1") (pintype "passive"))
      (node (ref "C1") (pin "2") (pinfunction "2_2") (pintype "passive"))
      (node (ref "C10") (pin "2") (pinfunction "2_2") (pintype "passive"))
      (node (ref "C11") (pin "2") (pinfunction "2_2") (pintype "passive"))
      (node (ref "C12") (pin "2") (pinfunction "2_2") (pintype "passive"))
      (node (ref "C13") (pin "2") (pinfunction "2_2") (pintype "passive"))
      (node (ref "C14") (pin "2") (pinfunction "2_2") (pintype "passive"))
      (node (ref "C15") (pin "2") (pinfunction "2_2") (pintype "passive"))
      (node (ref "C16") (pin "2") (pinfunction "2_2") (pintype "passive"))
      (node (ref "C17") (pin "2") (pinfunction "2_2") (pintype "passive"))
      (node (ref "C18") (pin "2") (pinfunction "2_2") (pintype "passive"))
      (node (ref "C19") (pin "2") (pinfunction "2_2") (pintype "passive"))
      (node (ref "C2") (pin "2") (pinfunction "2_2") (pintype "passive"))
      (node (ref "C20") (pin "2") (pinfunction "2_2") (pintype "passive"))
      (node (ref "C21") (pin "2") (pinfunction "2_2") (pintype "passive"))
      (node (ref "C22") (pin "1") (pinfunction "1_1") (pintype "passive"))
      (node (ref "C23") (pin "2") (pinfunction "2_2") (pintype "passive"))
      (node (ref "C24") (pin "2") (pinfunction "2_2") (pintype "passive"))
      (node (ref "C25") (pin "2") (pinfunction "2_2") (pintype "passive"))
      (node (ref "C26") (pin "2") (pinfunction "2_2") (pintype "passive"))
      (node (ref "C27") (pin "2") (pinfunction "2_2") (pintype "passive"))
      (node (ref "C28") (pin "2") (pinfunction "2_2") (pintype "passive"))
      (node (ref "C4") (pin "2") (pinfunction "2_2") (pintype "passive"))
      (node (ref "C5") (pin "2") (pinfunction "2_2") (pintype "passive"))
      (node (ref "C6") (pin "2") (pinfunction "2_2") (pintype "passive"))
      (node (ref "C7") (pin "2") (pinfunction "2_2") (pintype "passive"))
      (node (ref "C9") (pin "2") (pinfunction "2_2") (pintype "passive"))
      (node (ref "DWN") (pin "1") (pinfunction "1_1") (pintype "bidirectional"))
      (node (ref "DWN1") (pin "2") (pinfunction "2_2") (pintype "bidirectional"))
      (node (ref "DWN2") (pin "2") (pinfunction "2_2") (pintype "bidirectional"))
      (node (ref "GND") (pin "TP") (pinfunction "TP_TP") (pintype "input"))
      (node (ref "IC2") (pin "4") (pinfunction "VSS_4") (pintype "bidirectional"))
      (node (ref "NCREED3") (pin "TP") (pinfunction "TP_TP") (pintype "input"))
      (node (ref "Q1") (pin "2") (pinfunction "S_2") (pintype "passive"))
      (node (ref "Q3") (pin "2") (pinfunction "S_2") (pintype "passive"))
      (node (ref "R1") (pin "1") (pinfunction "1_1") (pintype "passive"))
      (node (ref "R10") (pin "1") (pinfunction "1_1") (pintype "passive"))
      (node (ref "R12") (pin "1") (pinfunction "1_1") (pintype "passive"))
      (node (ref "R3") (pin "1") (pinfunction "1_1") (pintype "passive"))
      (node (ref "R4") (pin "1") (pinfunction "1_1") (pintype "passive"))
      (node (ref "R7") (pin "1") (pinfunction "1_1") (pintype "passive"))
      (node (ref "R9") (pin "2") (pinfunction "2_2") (pintype "passive"))
      (node (ref "U$2") (pin "10") (pinfunction "VSSA_10") (pintype "bidirectional"))
      (node (ref "U$2") (pin "9") (pinfunction "VSS_9") (pintype "bidirectional"))
      (node (ref "U$45") (pin "CSB") (pinfunction "CSB_CSB") (pintype "bidirectional"))
      (node (ref "U$45") (pin "GND") (pinfunction "GND_GND") (pintype "bidirectional"))
      (node (ref "U$6") (pin "H1") (pinfunction "P$5_H1") (pintype "bidirectional"))
      (node (ref "U$6") (pin "H2") (pinfunction "P$6_H2") (pintype "bidirectional"))
      (node (ref "U$7") (pin "1") (pinfunction "SDO_1") (pintype "bidirectional"))
      (node (ref "U$7") (pin "8") (pinfunction "GNDIO_8") (pintype "bidirectional"))
      (node (ref "U$7") (pin "9") (pinfunction "GND_9") (pintype "bidirectional"))
      (node (ref "U1") (pin "3") (pinfunction "VSS_3") (pintype "bidirectional"))
      (node (ref "U1") (pin "EP") (pinfunction "PWPD_EP") (pintype "bidirectional"))
      (node (ref "U1") (pin "EP1") (pinfunction "PWPD_EP1") (pintype "bidirectional"))
      (node (ref "U1") (pin "EP2") (pinfunction "PWPD_EP2") (pintype "bidirectional"))
      (node (ref "U1") (pin "EP3") (pinfunction "PWPD_EP3") (pintype "bidirectional"))
      (node (ref "U1") (pin "EP4") (pinfunction "PWPD_EP4") (pintype "bidirectional"))
      (node (ref "U2") (pin "2") (pinfunction "GND_2") (pintype "power_in"))
      (node (ref "U2") (pin "4") (pinfunction "P4_4") (pintype "bidirectional"))
      (node (ref "U3") (pin "2") (pinfunction "VSS_2") (pintype "power_in"))
      (node (ref "U4") (pin "P$B7") (pinfunction "VSS_P$B7") (pintype "power_in"))
      (node (ref "U4") (pin "P$F23") (pinfunction "VSS_PA_P$F23") (pintype "bidirectional"))
      (node (ref "U4") (pin "THERMPAD") (pinfunction "VSS_PAD_THERMPAD") (pintype "bidirectional"))
    )
    (net (code "60") (name "GPOUT") (class "Default")
      (node (ref "R15") (pin "2") (pinfunction "2_2") (pintype "passive"))
      (node (ref "U1") (pin "12") (pinfunction "GPOUT_12") (pintype "bidirectional"))
    )
    (net (code "61") (name "Net-(-6-PP)") (class "Default")
      (node (ref "-6") (pin "TP") (pinfunction "PP_TP") (pintype "input"))
      (node (ref "Q4") (pin "3") (pinfunction "D_3") (pintype "passive"))
    )
    (net (code "62") (name "Net-(ANT-PP)") (class "Default")
      (node (ref "ANT") (pin "TP") (pinfunction "PP_TP") (pintype "input"))
      (node (ref "ANT1") (pin "TP") (pinfunction "PP_TP") (pintype "input"))
      (node (ref "C29") (pin "1") (pinfunction "1_1") (pintype "passive"))
    )
    (net (code "63") (name "Net-(C8-Pad1)") (class "Default")
      (node (ref "C8") (pin "1") (pinfunction "1_1") (pintype "passive"))
      (node (ref "DWN3") (pin "1") (pinfunction "1_1") (pintype "bidirectional"))
      (node (ref "R11") (pin "2") (pinfunction "2_2") (pintype "passive"))
    )
    (net (code "64") (name "Net-(D+-PadTP)") (class "Default")
      (node (ref "D+") (pin "TP") (pinfunction "TP_TP") (pintype "input"))
      (node (ref "R5") (pin "1") (pinfunction "1_1") (pintype "passive"))
    )
    (net (code "65") (name "Net-(D--PadTP)") (class "Default")
      (node (ref "D-") (pin "TP") (pinfunction "TP_TP") (pintype "input"))
      (node (ref "R2") (pin "1") (pinfunction "1_1") (pintype "passive"))
    )
    (net (code "66") (name "Net-(L3-Pad2)") (class "Default")
      (node (ref "L3") (pin "2") (pinfunction "2_2") (pintype "passive"))
      (node (ref "L4") (pin "1") (pinfunction "1_1") (pintype "passive"))
    )
    (net (code "67") (name "Net-(M1-PP)") (class "Default")
      (node (ref "C3") (pin "2") (pinfunction "2_2") (pintype "passive"))
      (node (ref "D1") (pin "A") (pinfunction "A_A") (pintype "passive"))
      (node (ref "M1") (pin "TP") (pinfunction "PP_TP") (pintype "input"))
      (node (ref "Q1") (pin "3") (pinfunction "D_3") (pintype "passive"))
    )
    (net (code "68") (name "Net-(M2-PP)") (class "Default")
      (node (ref "C3") (pin "1") (pinfunction "1_1") (pintype "passive"))
      (node (ref "D1") (pin "C") (pinfunction "C_C") (pintype "passive"))
      (node (ref "M2") (pin "TP") (pinfunction "PP_TP") (pintype "input"))
      (node (ref "R8") (pin "1") (pinfunction "1_1") (pintype "passive"))
    )
    (net (code "69") (name "Net-(Q3-D)") (class "Default")
      (node (ref "Q3") (pin "3") (pinfunction "D_3") (pintype "passive"))
      (node (ref "U$6") (pin "1") (pinfunction "1_1") (pintype "bidirectional"))
      (node (ref "U$6") (pin "2") (pinfunction "2_2") (pintype "bidirectional"))
    )
    (net (code "70") (name "Net-(R21-Pad1)") (class "Default")
      (node (ref "R21") (pin "1") (pinfunction "1_1") (pintype "passive"))
      (node (ref "U$6") (pin "3") (pinfunction "3_3") (pintype "bidirectional"))
      (node (ref "U$6") (pin "4") (pinfunction "4_4") (pintype "bidirectional"))
    )
    (net (code "71") (name "Net-(U3-PROG)") (class "Default")
      (node (ref "R4") (pin "2") (pinfunction "2_2") (pintype "passive"))
      (node (ref "U3") (pin "5") (pinfunction "PROG_5") (pintype "input"))
    )
    (net (code "72") (name "Net-(U4-ANT)") (class "Default")
      (node (ref "C12") (pin "1") (pinfunction "1_1") (pintype "passive"))
      (node (ref "L2") (pin "1") (pinfunction "1_1") (pintype "passive"))
      (node (ref "U4") (pin "P$H23") (pinfunction "ANT_P$H23") (pintype "bidirectional"))
    )
    (net (code "73") (name "Net-(U4-DCC)") (class "Default")
      (node (ref "L3") (pin "1") (pinfunction "1_1") (pintype "passive"))
      (node (ref "U4") (pin "P$B3") (pinfunction "DCC_P$B3") (pintype "output"))
    )
    (net (code "74") (name "Net-(U4-DCCH)") (class "Default")
      (node (ref "L5") (pin "1") (pinfunction "1_1") (pintype "passive"))
      (node (ref "U4") (pin "P$AB2") (pinfunction "DCCH_P$AB2") (pintype "bidirectional"))
    )
    (net (code "75") (name "Net-(U4-XC1)") (class "Default")
      (node (ref "C16") (pin "1") (pinfunction "1_1") (pintype "passive"))
      (node (ref "U4") (pin "P$B24") (pinfunction "XC1_P$B24") (pintype "input"))
      (node (ref "Y1") (pin "1") (pinfunction "1_1") (pintype "passive"))
    )
    (net (code "76") (name "Net-(U4-XC2)") (class "Default")
      (node (ref "C15") (pin "1") (pinfunction "1_1") (pintype "passive"))
      (node (ref "U4") (pin "P$A23") (pinfunction "XC2_P$A23") (pintype "output"))
      (node (ref "Y1") (pin "3") (pinfunction "2_3") (pintype "passive"))
    )
    (net (code "77") (name "SCL") (class "Default")
      (node (ref "-2") (pin "TP") (pinfunction "PP_TP") (pintype "input"))
      (node (ref "R14") (pin "1") (pinfunction "1_1") (pintype "passive"))
      (node (ref "U$45") (pin "SCL") (pinfunction "SCL_SCL") (pintype "bidirectional"))
      (node (ref "U$7") (pin "12") (pinfunction "SCX_12") (pintype "bidirectional"))
      (node (ref "U1") (pin "2") (pinfunction "SCL_2") (pintype "bidirectional"))
      (node (ref "U4") (pin "P$T2") (pinfunction "P0.11_P$T2") (pintype "bidirectional"))
    )
    (net (code "78") (name "SDA") (class "Default")
      (node (ref "-3") (pin "TP") (pinfunction "PP_TP") (pintype "input"))
      (node (ref "R13") (pin "1") (pinfunction "1_1") (pintype "passive"))
      (node (ref "U$45") (pin "SDA") (pinfunction "SDA_SDA") (pintype "bidirectional"))
      (node (ref "U$7") (pin "2") (pinfunction "SDX_2") (pintype "bidirectional"))
      (node (ref "U1") (pin "1") (pinfunction "SDA_1") (pintype "bidirectional"))
      (node (ref "U4") (pin "P$U1") (pinfunction "P0.12_P$U1") (pintype "bidirectional"))
    )
    (net (code "79") (name "TS") (class "Default")
      (node (ref "R9") (pin "1") (pinfunction "1_1") (pintype "passive"))
      (node (ref "U1") (pin "10") (pinfunction "BIN_10") (pintype "bidirectional"))
    )
    (net (code "80") (name "VBAT") (class "Default")
      (node (ref "+") (pin "TP") (pinfunction "PP_TP") (pintype "input"))
      (node (ref "C6") (pin "1") (pinfunction "1_1") (pintype "passive"))
      (node (ref "Q5") (pin "3") (pinfunction "D_3") (pintype "passive"))
      (node (ref "R6") (pin "1") (pinfunction "1_1") (pintype "passive"))
      (node (ref "U1") (pin "7") (pinfunction "SRN_7") (pintype "bidirectional"))
      (node (ref "U3") (pin "3") (pinfunction "VBAT_3") (pintype "power_in"))
    )
    (net (code "81") (name "VBUS") (class "Default")
      (node (ref "D2") (pin "A") (pinfunction "A_A") (pintype "passive"))
      (node (ref "Q5") (pin "1") (pinfunction "G_1") (pintype "passive"))
      (node (ref "R3") (pin "2") (pinfunction "2_2") (pintype "passive"))
      (node (ref "U3") (pin "4") (pinfunction "VDD_4") (pintype "power_in"))
      (node (ref "U4") (pin "P$AD2") (pinfunction "VBUS_P$AD2") (pintype "power_in"))
      (node (ref "VBUS") (pin "TP") (pinfunction "TP_TP") (pintype "input"))
    )
    (net (code "82") (name "unconnected-(DWN-FRM-PadFRAME)") (class "Default")
      (node (ref "DWN") (pin "FRAME") (pinfunction "FRM_FRAME") (pintype "bidirectional"))
    )
    (net (code "83") (name "unconnected-(DWN1-FRM-PadFRAME)") (class "Default")
      (node (ref "DWN1") (pin "FRAME") (pinfunction "FRM_FRAME") (pintype "bidirectional"))
    )
    (net (code "84") (name "unconnected-(DWN2-FRM-PadFRAME)") (class "Default")
      (node (ref "DWN2") (pin "FRAME") (pinfunction "FRM_FRAME") (pintype "bidirectional"))
    )
    (net (code "85") (name "unconnected-(DWN3-FRM-PadFRAME)") (class "Default")
      (node (ref "DWN3") (pin "FRAME") (pinfunction "FRM_FRAME") (pintype "bidirectional"))
    )
    (net (code "86") (name "unconnected-(U$7-NC-Pad4)") (class "Default")
      (node (ref "U$7") (pin "4") (pinfunction "NC_4") (pintype "bidirectional"))
    )
    (net (code "87") (name "unconnected-(U$7-NC2-Pad11)") (class "Default")
      (node (ref "U$7") (pin "11") (pinfunction "NC2_11") (pintype "bidirectional"))
    )
    (net (code "88") (name "unconnected-(U$45-PadCSB2)") (class "Default")
      (node (ref "U$45") (pin "CSB2") (pinfunction "CSB2_CSB2") (pintype "bidirectional"))
    )
    (net (code "89") (name "unconnected-(U$45-PadSDO)") (class "Default")
      (node (ref "U$45") (pin "SDO") (pinfunction "SDO_SDO") (pintype "bidirectional"))
    )
    (net (code "90") (name "unconnected-(U4-DEC2-PadP$A18)") (class "Default")
      (node (ref "U4") (pin "P$A18") (pinfunction "DEC2_P$A18") (pintype "bidirectional"))
    )
    (net (code "91") (name "unconnected-(U4-P0.09{slash}NFC1-PadP$L24)") (class "Default")
      (node (ref "U4") (pin "P$L24") (pinfunction "P0.09/NFC1_P$L24") (pintype "bidirectional"))
    )
    (net (code "92") (name "unconnected-(U4-P0.10{slash}NFC2-PadP$J24)") (class "Default")
      (node (ref "U4") (pin "P$J24") (pinfunction "P0.10/NFC2_P$J24") (pintype "bidirectional"))
    )
    (net (code "93") (name "unconnected-(U4-P1.01-PadP$Y23)") (class "Default")
      (node (ref "U4") (pin "P$Y23") (pinfunction "P1.01_P$Y23") (pintype "bidirectional"))
    )
    (net (code "94") (name "unconnected-(U4-P1.03-PadP$V23)") (class "Default")
      (node (ref "U4") (pin "P$V23") (pinfunction "P1.03_P$V23") (pintype "bidirectional"))
    )
    (net (code "95") (name "unconnected-(U4-P1.05-PadP$T23)") (class "Default")
      (node (ref "U4") (pin "P$T23") (pinfunction "P1.05_P$T23") (pintype "bidirectional"))
    )
    (net (code "96") (name "unconnected-(U4-P1.07-PadP$P23)") (class "Default")
      (node (ref "U4") (pin "P$P23") (pinfunction "P1.07_P$P23") (pintype "bidirectional"))
    )
    (net (code "97") (name "unconnected-(U4-P1.11-PadP$B19)") (class "Default")
      (node (ref "U4") (pin "P$B19") (pinfunction "P1.11_P$B19") (pintype "bidirectional"))
    )
  )
)
